# SparkFun_ProDriver_TC78H670FTG.net
KiCad netlist of a schematic drawn in EAGLE
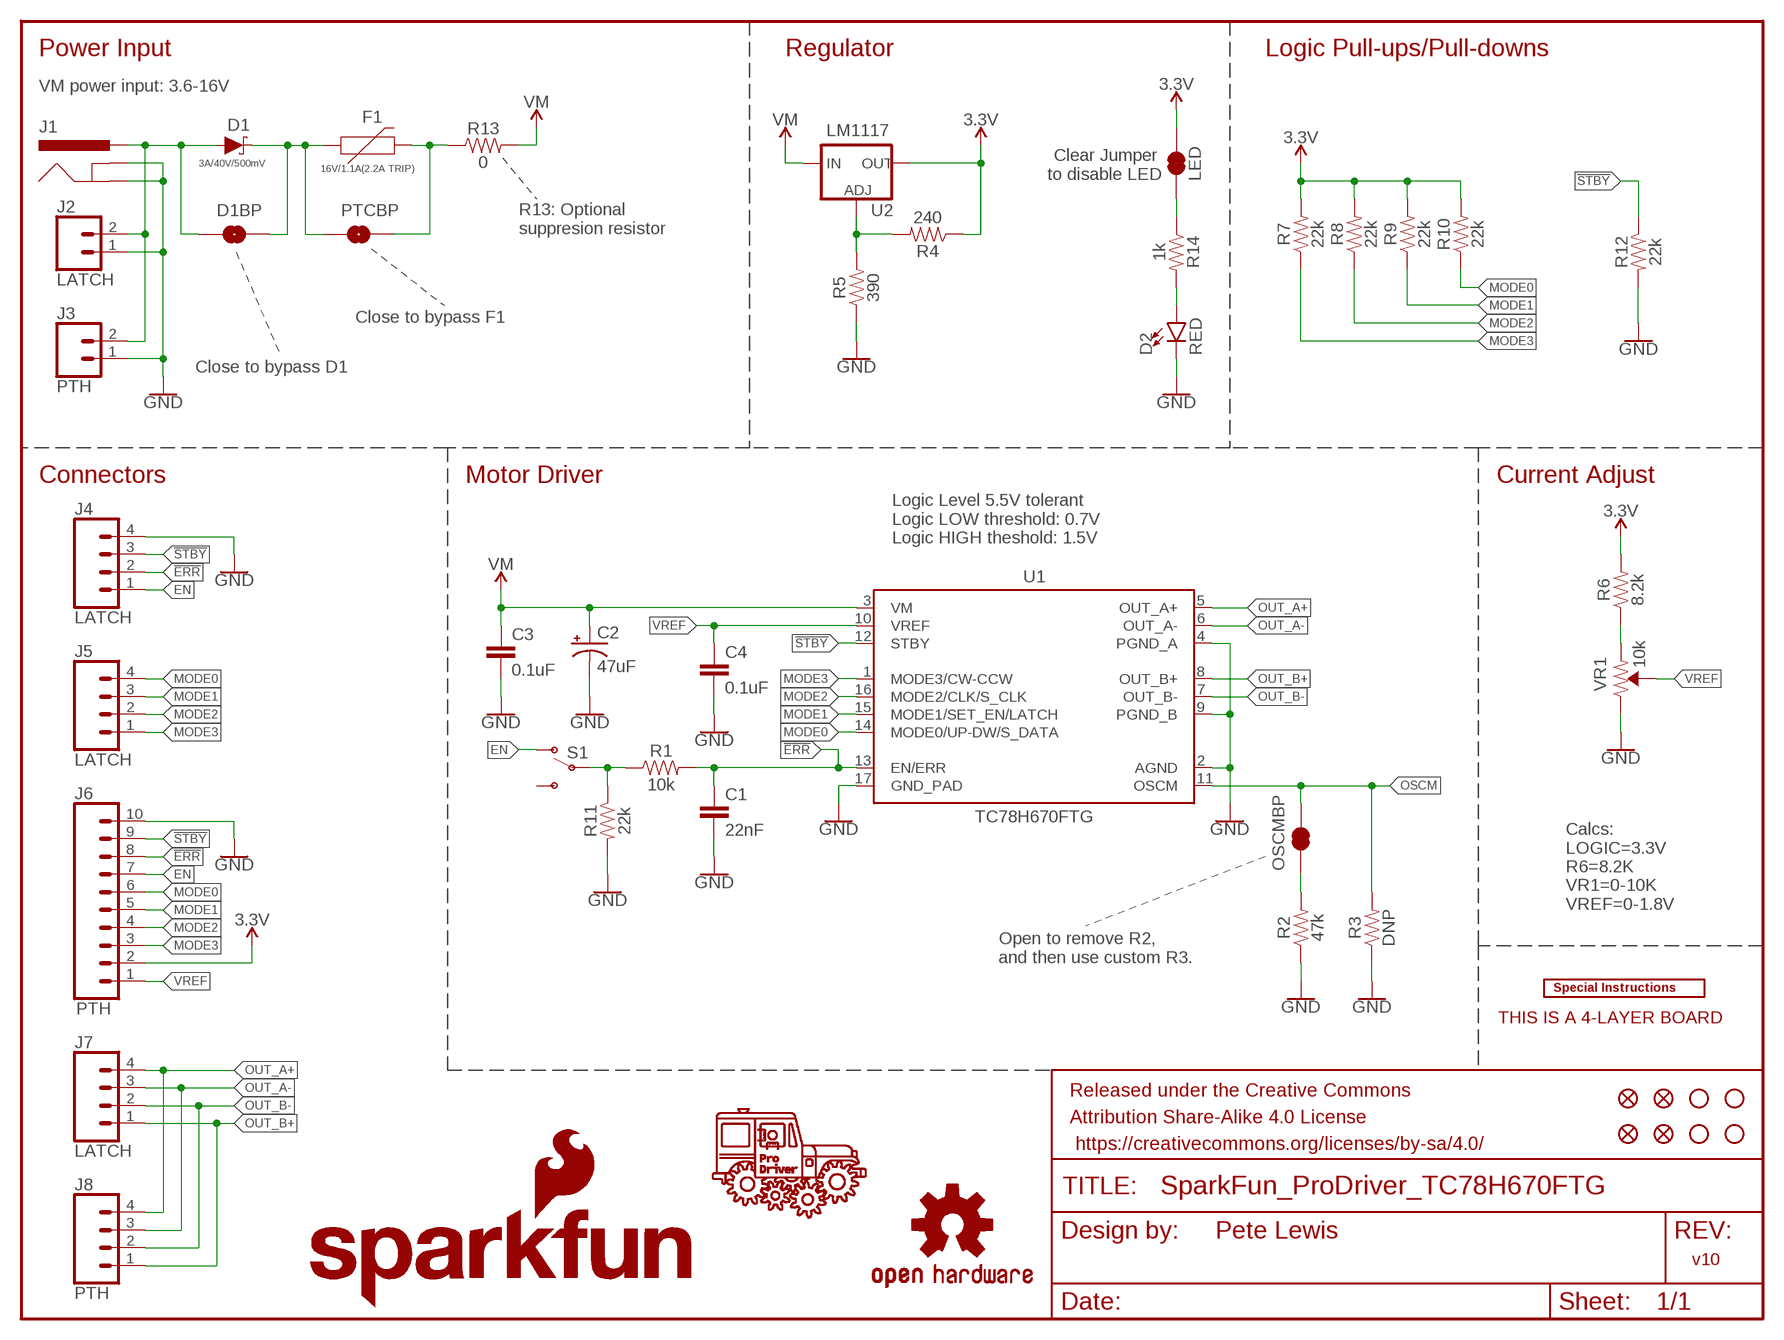
[diagram p0: schematic, sheet 1]

(export (version "E")
  (design (tool "Eeschema 10.0.6"))
  (components
    (comp (ref "C1")
      (value "22nF")
      (footprint "eagle-import:0603")
      (libsource (lib "eagle-import") (part "22NF/22,000PF-0603-50V-10%"))
    )
    (comp (ref "C2")
      (value "47uF")
      (footprint "eagle-import:PANASONIC_D")
      (libsource (lib "eagle-import") (part "47UF-POLAR-PANASONIC_D-35V-20%"))
    )
    (comp (ref "C3")
      (value "0.1uF")
      (footprint "eagle-import:0603")
      (libsource (lib "eagle-import") (part "0.1UF-0603-25V-(+80/-20%)"))
    )
    (comp (ref "C4")
      (value "0.1uF")
      (footprint "eagle-import:0603")
      (libsource (lib "eagle-import") (part "0.1UF-0603-25V-(+80/-20%)"))
    )
    (comp (ref "D1")
      (value "3A/40V/500mV")
      (footprint "eagle-import:SMA-DIODE")
      (libsource (lib "eagle-import") (part "DIODE-SCHOTTKY-B340A"))
    )
    (comp (ref "D1BP")
      (value "JUMPER-SMT_2_NO_SILK")
      (footprint "eagle-import:SMT-JUMPER_2_NO_SILK")
      (libsource (lib "eagle-import") (part "JUMPER-SMT_2_NO_SILK"))
    )
    (comp (ref "D2")
      (value "RED")
      (footprint "eagle-import:LED-0603")
      (libsource (lib "eagle-import") (part "LED-RED0603"))
    )
    (comp (ref "F1")
      (value "16V/1.1A(2.2A TRIP)")
      (footprint "eagle-import:1210")
      (libsource (lib "eagle-import") (part "PPTC_16V_1.1A_(2.2ATRIP)"))
    )
    (comp (ref "FID1")
      (value "FIDUCIAL1X2")
      (footprint "eagle-import:FIDUCIAL-1X2")
      (libsource (lib "eagle-import") (part "FIDUCIAL1X2"))
    )
    (comp (ref "FID2")
      (value "FIDUCIAL1X2")
      (footprint "eagle-import:FIDUCIAL-1X2")
      (libsource (lib "eagle-import") (part "FIDUCIAL1X2"))
    )
    (comp (ref "FID3")
      (value "FIDUCIAL1X2")
      (footprint "eagle-import:FIDUCIAL-1X2")
      (libsource (lib "eagle-import") (part "FIDUCIAL1X2"))
    )
    (comp (ref "FID4")
      (value "FIDUCIAL1X2")
      (footprint "eagle-import:FIDUCIAL-1X2")
      (libsource (lib "eagle-import") (part "FIDUCIAL1X2"))
    )
    (comp (ref "FRAME1")
      (value "FRAME-LETTER")
      (footprint "eagle-import:CREATIVE_COMMONS")
      (libsource (lib "eagle-import") (part "FRAME-LETTER"))
    )
    (comp (ref "J1")
      (value "POWER_JACKTOE")
      (footprint "eagle-import:POWER_JACK_SMD_OVERPASTE_TOE")
      (libsource (lib "eagle-import") (part "POWER_JACKTOE"))
    )
    (comp (ref "J2")
      (value "LATCH")
      (footprint "eagle-import:LATCHTERMINAL-5MM-2")
      (libsource (lib "eagle-import") (part "CONN_02LATCH_2"))
    )
    (comp (ref "J3")
      (value "PTH")
      (footprint "eagle-import:1X02_NO_SILK")
      (libsource (lib "eagle-import") (part "CONN_021X02_NO_SILK"))
    )
    (comp (ref "J4")
      (value "LATCH")
      (footprint "eagle-import:LATCHTERMINAL-5MM-4")
      (libsource (lib "eagle-import") (part "CONN_04LATCH"))
    )
    (comp (ref "J5")
      (value "LATCH")
      (footprint "eagle-import:LATCHTERMINAL-5MM-4")
      (libsource (lib "eagle-import") (part "CONN_04LATCH"))
    )
    (comp (ref "J6")
      (value "PTH")
      (footprint "eagle-import:1X10_NO_SILK")
      (libsource (lib "eagle-import") (part "CONN_10NO_SILK_PTH_FEMALE"))
    )
    (comp (ref "J7")
      (value "LATCH")
      (footprint "eagle-import:LATCHTERMINAL-5MM-4")
      (libsource (lib "eagle-import") (part "CONN_04LATCH"))
    )
    (comp (ref "J8")
      (value "PTH")
      (footprint "eagle-import:1X04_NO_SILK")
      (libsource (lib "eagle-import") (part "CONN_041X04_NO_SILK"))
    )
    (comp (ref "JP4")
      (value "LED")
      (footprint "eagle-import:SMT-JUMPER_2_NC_TRACE_SILK")
      (libsource (lib "eagle-import") (part "JUMPER-SMT_2_NC_TRACE_SILK"))
    )
    (comp (ref "LOGO1")
      (value "SFE_LOGO_NAME_FLAME.1_INCH")
      (footprint "eagle-import:SFE_LOGO_NAME_FLAME_.1")
      (libsource (lib "eagle-import") (part "SFE_LOGO_NAME_FLAME.1_INCH"))
    )
    (comp (ref "LOGO2")
      (value "OSHW-LOGOS")
      (footprint "eagle-import:OSHW-LOGO-S")
      (libsource (lib "eagle-import") (part "OSHW-LOGOS"))
    )
    (comp (ref "LOGO3")
      (value "SPECIAL_INSTRUCTIONS-ORDERING")
      (footprint "eagle-import:ORDERING_INSTRUCTIONS")
      (libsource (lib "eagle-import") (part "SPECIAL_INSTRUCTIONS-ORDERING"))
    )
    (comp (ref "OSCMBP")
      (value "JUMPER-SMT_2_NC_TRACE_SILK")
      (footprint "eagle-import:SMT-JUMPER_2_NC_TRACE_SILK")
      (libsource (lib "eagle-import") (part "JUMPER-SMT_2_NC_TRACE_SILK"))
    )
    (comp (ref "PTCBP")
      (value "JUMPER-SMT_2_NO_SILK")
      (footprint "eagle-import:SMT-JUMPER_2_NO_SILK")
      (libsource (lib "eagle-import") (part "JUMPER-SMT_2_NO_SILK"))
    )
    (comp (ref "R1")
      (value "10k")
      (footprint "eagle-import:0603")
      (libsource (lib "eagle-import") (part "10KOHM-0603-1/10W-1%"))
    )
    (comp (ref "R2")
      (value "47k")
      (footprint "eagle-import:0603")
      (libsource (lib "eagle-import") (part "47KOHM-0603-1/10W-1%"))
    )
    (comp (ref "R3")
      (value "DNP")
      (footprint "eagle-import:AXIAL-0.3")
      (libsource (lib "eagle-import") (part "RESISTORAXIAL-0.3"))
    )
    (comp (ref "R4")
      (value "240")
      (footprint "eagle-import:0603")
      (libsource (lib "eagle-import") (part "240OHM-0603-1/10W-1%"))
    )
    (comp (ref "R5")
      (value "390")
      (footprint "eagle-import:0603")
      (libsource (lib "eagle-import") (part "390OHM-0603-1/10W-1%"))
    )
    (comp (ref "R6")
      (value "8.2k")
      (footprint "eagle-import:0603")
      (libsource (lib "eagle-import") (part "8.2KOHM-0603-1/10W-5%"))
    )
    (comp (ref "R7")
      (value "22k")
      (footprint "eagle-import:0603")
      (libsource (lib "eagle-import") (part "22KOHM-0603-1/10W-1%"))
    )
    (comp (ref "R8")
      (value "22k")
      (footprint "eagle-import:0603")
      (libsource (lib "eagle-import") (part "22KOHM-0603-1/10W-1%"))
    )
    (comp (ref "R9")
      (value "22k")
      (footprint "eagle-import:0603")
      (libsource (lib "eagle-import") (part "22KOHM-0603-1/10W-1%"))
    )
    (comp (ref "R10")
      (value "22k")
      (footprint "eagle-import:0603")
      (libsource (lib "eagle-import") (part "22KOHM-0603-1/10W-1%"))
    )
    (comp (ref "R11")
      (value "22k")
      (footprint "eagle-import:0603")
      (libsource (lib "eagle-import") (part "22KOHM-0603-1/10W-1%"))
    )
    (comp (ref "R12")
      (value "22k")
      (footprint "eagle-import:0603")
      (libsource (lib "eagle-import") (part "22KOHM-0603-1/10W-1%"))
    )
    (comp (ref "R13")
      (value "0")
      (footprint "eagle-import:0603")
      (libsource (lib "eagle-import") (part "0OHM-0603-1/10W-5%"))
    )
    (comp (ref "R14")
      (value "1k")
      (footprint "eagle-import:0603")
      (libsource (lib "eagle-import") (part "1KOHM-0603-1/10W-1%"))
    )
    (comp (ref "S1")
      (value "SWITCH-SPDT-PTH-11.6X4.0MM-LOCK")
      (footprint "eagle-import:SWITCH_SPDT_PTH_11.6X4.0MM_LOCK")
      (libsource (lib "eagle-import") (part "SWITCH-SPDT-PTH-11.6X4.0MM-LOCK"))
    )
    (comp (ref "STANDOFF1")
      (value "STAND-OFF")
      (footprint "eagle-import:STAND-OFF")
      (libsource (lib "eagle-import") (part "STAND-OFF"))
    )
    (comp (ref "STANDOFF2")
      (value "STAND-OFF")
      (footprint "eagle-import:STAND-OFF")
      (libsource (lib "eagle-import") (part "STAND-OFF"))
    )
    (comp (ref "STANDOFF3")
      (value "STAND-OFF")
      (footprint "eagle-import:STAND-OFF")
      (libsource (lib "eagle-import") (part "STAND-OFF"))
    )
    (comp (ref "STANDOFF4")
      (value "STAND-OFF")
      (footprint "eagle-import:STAND-OFF")
      (libsource (lib "eagle-import") (part "STAND-OFF"))
    )
    (comp (ref "U$41")
      (value "PRODRIVER_LOGO")
      (footprint "eagle-import:PRODRIVER_LOGO")
      (libsource (lib "eagle-import") (part "PRODRIVER_LOGO"))
    )
    (comp (ref "U1")
      (value "TC78H670FTG")
      (footprint "eagle-import:P-VQFN16-0303-0.50-001")
      (libsource (lib "eagle-import") (part "TC78H670FTG"))
    )
    (comp (ref "U2")
      (value "LM1117")
      (footprint "eagle-import:SOT223")
      (libsource (lib "eagle-import") (part "V_REG_LM1117SOT223"))
    )
    (comp (ref "VR1")
      (value "10k")
      (footprint "eagle-import:TRIMPOT-SMD-3MM-CLOSED")
      (libsource (lib "eagle-import") (part "TRIMPOT-SMD-3MM-CLOSED-1/8W-20%"))
    )
  )
  (nets
    (net (code "1") (name "/~{ERR}") (class "Default")
      (node (ref "C1") (pin "1") (pinfunction "1_1") (pintype "passive"))
      (node (ref "J4") (pin "2") (pinfunction "2_2") (pintype "passive"))
      (node (ref "J6") (pin "8") (pinfunction "8_8") (pintype "passive"))
      (node (ref "R1") (pin "2") (pinfunction "2_2") (pintype "passive"))
      (node (ref "U1") (pin "13") (pinfunction "EN/ERR_13") (pintype "bidirectional"))
    )
    (net (code "2") (name "/~{STBY}") (class "Default")
      (node (ref "J4") (pin "3") (pinfunction "3_3") (pintype "passive"))
      (node (ref "J6") (pin "9") (pinfunction "9_9") (pintype "passive"))
      (node (ref "R12") (pin "1") (pinfunction "1_1") (pintype "passive"))
      (node (ref "U1") (pin "12") (pinfunction "STBY_12") (pintype "bidirectional"))
    )
    (net (code "3") (name "3.3V") (class "Default")
      (node (ref "J6") (pin "2") (pinfunction "2_2") (pintype "passive"))
      (node (ref "JP4") (pin "2") (pinfunction "2_2") (pintype "passive"))
      (node (ref "R10") (pin "2") (pinfunction "2_2") (pintype "passive"))
      (node (ref "R4") (pin "1") (pinfunction "1_1") (pintype "passive"))
      (node (ref "R6") (pin "2") (pinfunction "2_2") (pintype "passive"))
      (node (ref "R7") (pin "2") (pinfunction "2_2") (pintype "passive"))
      (node (ref "R8") (pin "2") (pinfunction "2_2") (pintype "passive"))
      (node (ref "R9") (pin "2") (pinfunction "2_2") (pintype "passive"))
      (node (ref "U2") (pin "2") (pinfunction "OUT_2") (pintype "output"))
      (node (ref "U2") (pin "4") (pinfunction "OUT_4") (pintype "output"))
    )
    (net (code "4") (name "EN") (class "Default")
      (node (ref "J4") (pin "1") (pinfunction "1_1") (pintype "passive"))
      (node (ref "J6") (pin "7") (pinfunction "7_7") (pintype "passive"))
      (node (ref "S1") (pin "1") (pinfunction "O_1") (pintype "passive"))
    )
    (net (code "5") (name "GND") (class "Default")
      (node (ref "C1") (pin "2") (pinfunction "2_2") (pintype "passive"))
      (node (ref "C2") (pin "-") (pinfunction "-_-") (pintype "passive"))
      (node (ref "C3") (pin "2") (pinfunction "2_2") (pintype "passive"))
      (node (ref "C4") (pin "2") (pinfunction "2_2") (pintype "passive"))
      (node (ref "D2") (pin "C") (pinfunction "C_C") (pintype "passive"))
      (node (ref "J1") (pin "GND") (pinfunction "GNDBREAK_GND") (pintype "bidirectional"))
      (node (ref "J1") (pin "P$4") (pinfunction "GND_P$4") (pintype "bidirectional"))
      (node (ref "J2") (pin "1") (pinfunction "1_1") (pintype "passive"))
      (node (ref "J3") (pin "1") (pinfunction "1_1") (pintype "passive"))
      (node (ref "J4") (pin "4") (pinfunction "4_4") (pintype "passive"))
      (node (ref "J6") (pin "10") (pinfunction "10_10") (pintype "passive"))
      (node (ref "R11") (pin "2") (pinfunction "2_2") (pintype "passive"))
      (node (ref "R12") (pin "2") (pinfunction "2_2") (pintype "passive"))
      (node (ref "R2") (pin "1") (pinfunction "1_1") (pintype "passive"))
      (node (ref "R3") (pin "P$1") (pinfunction "1_P$1") (pintype "passive"))
      (node (ref "R5") (pin "1") (pinfunction "1_1") (pintype "passive"))
      (node (ref "U1") (pin "17") (pinfunction "GND_PAD_17") (pintype "bidirectional"))
      (node (ref "U1") (pin "2") (pinfunction "AGND_2") (pintype "bidirectional"))
      (node (ref "U1") (pin "4") (pinfunction "PGND_A_4") (pintype "bidirectional"))
      (node (ref "U1") (pin "9") (pinfunction "PGND_B_9") (pintype "bidirectional"))
      (node (ref "VR1") (pin "3") (pinfunction "CW_3") (pintype "passive"))
    )
    (net (code "6") (name "MODE0") (class "Default")
      (node (ref "J5") (pin "4") (pinfunction "4_4") (pintype "passive"))
      (node (ref "J6") (pin "6") (pinfunction "6_6") (pintype "passive"))
      (node (ref "R10") (pin "1") (pinfunction "1_1") (pintype "passive"))
      (node (ref "U1") (pin "14") (pinfunction "MODE0/UP-DW/S_DATA_14") (pintype "bidirectional"))
    )
    (net (code "7") (name "MODE1") (class "Default")
      (node (ref "J5") (pin "3") (pinfunction "3_3") (pintype "passive"))
      (node (ref "J6") (pin "5") (pinfunction "5_5") (pintype "passive"))
      (node (ref "R9") (pin "1") (pinfunction "1_1") (pintype "passive"))
      (node (ref "U1") (pin "15") (pinfunction "MODE1/SET_EN/LATCH_15") (pintype "bidirectional"))
    )
    (net (code "8") (name "MODE2") (class "Default")
      (node (ref "J5") (pin "2") (pinfunction "2_2") (pintype "passive"))
      (node (ref "J6") (pin "4") (pinfunction "4_4") (pintype "passive"))
      (node (ref "R8") (pin "1") (pinfunction "1_1") (pintype "passive"))
      (node (ref "U1") (pin "16") (pinfunction "MODE2/CLK/S_CLK_16") (pintype "bidirectional"))
    )
    (net (code "9") (name "MODE3") (class "Default")
      (node (ref "J5") (pin "1") (pinfunction "1_1") (pintype "passive"))
      (node (ref "J6") (pin "3") (pinfunction "3_3") (pintype "passive"))
      (node (ref "R7") (pin "1") (pinfunction "1_1") (pintype "passive"))
      (node (ref "U1") (pin "1") (pinfunction "MODE3/CW-CCW_1") (pintype "bidirectional"))
    )
    (net (code "10") (name "Net-(D1-PadC)") (class "Default")
      (node (ref "D1") (pin "C") (pinfunction "C_C") (pintype "passive"))
      (node (ref "D1BP") (pin "2") (pinfunction "2_2") (pintype "passive"))
      (node (ref "F1") (pin "1") (pinfunction "1_1") (pintype "bidirectional"))
      (node (ref "PTCBP") (pin "1") (pinfunction "1_1") (pintype "passive"))
    )
    (net (code "11") (name "Net-(D2-PadA)") (class "Default")
      (node (ref "D2") (pin "A") (pinfunction "A_A") (pintype "passive"))
      (node (ref "R14") (pin "2") (pinfunction "2_2") (pintype "passive"))
    )
    (net (code "12") (name "Net-(F1-Pad2)") (class "Default")
      (node (ref "F1") (pin "2") (pinfunction "2_2") (pintype "bidirectional"))
      (node (ref "PTCBP") (pin "2") (pinfunction "2_2") (pintype "passive"))
      (node (ref "R13") (pin "1") (pinfunction "1_1") (pintype "passive"))
    )
    (net (code "13") (name "Net-(J1-PWR)") (class "Default")
      (node (ref "D1") (pin "A") (pinfunction "A_A") (pintype "passive"))
      (node (ref "D1BP") (pin "1") (pinfunction "1_1") (pintype "passive"))
      (node (ref "J1") (pin "VIN0") (pinfunction "PWR_VIN0") (pintype "bidirectional"))
      (node (ref "J2") (pin "2") (pinfunction "2_2") (pintype "passive"))
      (node (ref "J3") (pin "2") (pinfunction "2_2") (pintype "passive"))
    )
    (net (code "14") (name "Net-(JP4-Pad1)") (class "Default")
      (node (ref "JP4") (pin "1") (pinfunction "1_1") (pintype "passive"))
      (node (ref "R14") (pin "1") (pinfunction "1_1") (pintype "passive"))
    )
    (net (code "15") (name "Net-(OSCMBP-Pad1)") (class "Default")
      (node (ref "OSCMBP") (pin "1") (pinfunction "1_1") (pintype "passive"))
      (node (ref "R2") (pin "2") (pinfunction "2_2") (pintype "passive"))
    )
    (net (code "16") (name "Net-(S1-P)") (class "Default")
      (node (ref "R1") (pin "1") (pinfunction "1_1") (pintype "passive"))
      (node (ref "R11") (pin "1") (pinfunction "1_1") (pintype "passive"))
      (node (ref "S1") (pin "2") (pinfunction "P_2") (pintype "passive"))
    )
    (net (code "17") (name "Net-(U2-ADJ)") (class "Default")
      (node (ref "R4") (pin "2") (pinfunction "2_2") (pintype "passive"))
      (node (ref "R5") (pin "2") (pinfunction "2_2") (pintype "passive"))
      (node (ref "U2") (pin "1") (pinfunction "ADJ_1") (pintype "input"))
    )
    (net (code "18") (name "Net-(VR1-CCW)") (class "Default")
      (node (ref "R6") (pin "1") (pinfunction "1_1") (pintype "passive"))
      (node (ref "VR1") (pin "1") (pinfunction "CCW_1") (pintype "passive"))
    )
    (net (code "19") (name "OSCM") (class "Default")
      (node (ref "OSCMBP") (pin "2") (pinfunction "2_2") (pintype "passive"))
      (node (ref "R3") (pin "P$2") (pinfunction "2_P$2") (pintype "passive"))
      (node (ref "U1") (pin "11") (pinfunction "OSCM_11") (pintype "bidirectional"))
    )
    (net (code "20") (name "OUT_A+") (class "Default")
      (node (ref "J7") (pin "4") (pinfunction "4_4") (pintype "passive"))
      (node (ref "J8") (pin "4") (pinfunction "4_4") (pintype "passive"))
      (node (ref "U1") (pin "5") (pinfunction "OUT_A+_5") (pintype "bidirectional"))
    )
    (net (code "21") (name "OUT_A-") (class "Default")
      (node (ref "J7") (pin "3") (pinfunction "3_3") (pintype "passive"))
      (node (ref "J8") (pin "3") (pinfunction "3_3") (pintype "passive"))
      (node (ref "U1") (pin "6") (pinfunction "OUT_A-_6") (pintype "bidirectional"))
    )
    (net (code "22") (name "OUT_B+") (class "Default")
      (node (ref "J7") (pin "1") (pinfunction "1_1") (pintype "passive"))
      (node (ref "J8") (pin "1") (pinfunction "1_1") (pintype "passive"))
      (node (ref "U1") (pin "8") (pinfunction "OUT_B+_8") (pintype "bidirectional"))
    )
    (net (code "23") (name "OUT_B-") (class "Default")
      (node (ref "J7") (pin "2") (pinfunction "2_2") (pintype "passive"))
      (node (ref "J8") (pin "2") (pinfunction "2_2") (pintype "passive"))
      (node (ref "U1") (pin "7") (pinfunction "OUT_B-_7") (pintype "bidirectional"))
    )
    (net (code "24") (name "VM") (class "Default")
      (node (ref "C2") (pin "+") (pinfunction "+_+") (pintype "passive"))
      (node (ref "C3") (pin "1") (pinfunction "1_1") (pintype "passive"))
      (node (ref "R13") (pin "2") (pinfunction "2_2") (pintype "passive"))
      (node (ref "U1") (pin "3") (pinfunction "VM_3") (pintype "bidirectional"))
      (node (ref "U2") (pin "3") (pinfunction "IN_3") (pintype "input"))
    )
    (net (code "25") (name "VREF") (class "Default")
      (node (ref "C4") (pin "1") (pinfunction "1_1") (pintype "passive"))
      (node (ref "J6") (pin "1") (pinfunction "1_1") (pintype "passive"))
      (node (ref "U1") (pin "10") (pinfunction "VREF_10") (pintype "bidirectional"))
      (node (ref "VR1") (pin "2") (pinfunction "WIPER_2") (pintype "passive"))
    )
    (net (code "26") (name "unconnected-(S1-S-Pad3)") (class "Default")
      (node (ref "S1") (pin "3") (pinfunction "S_3") (pintype "passive"))
    )
  )
)
